# schematic.net
KiCad netlist of a schematic drawn in Altium Designer
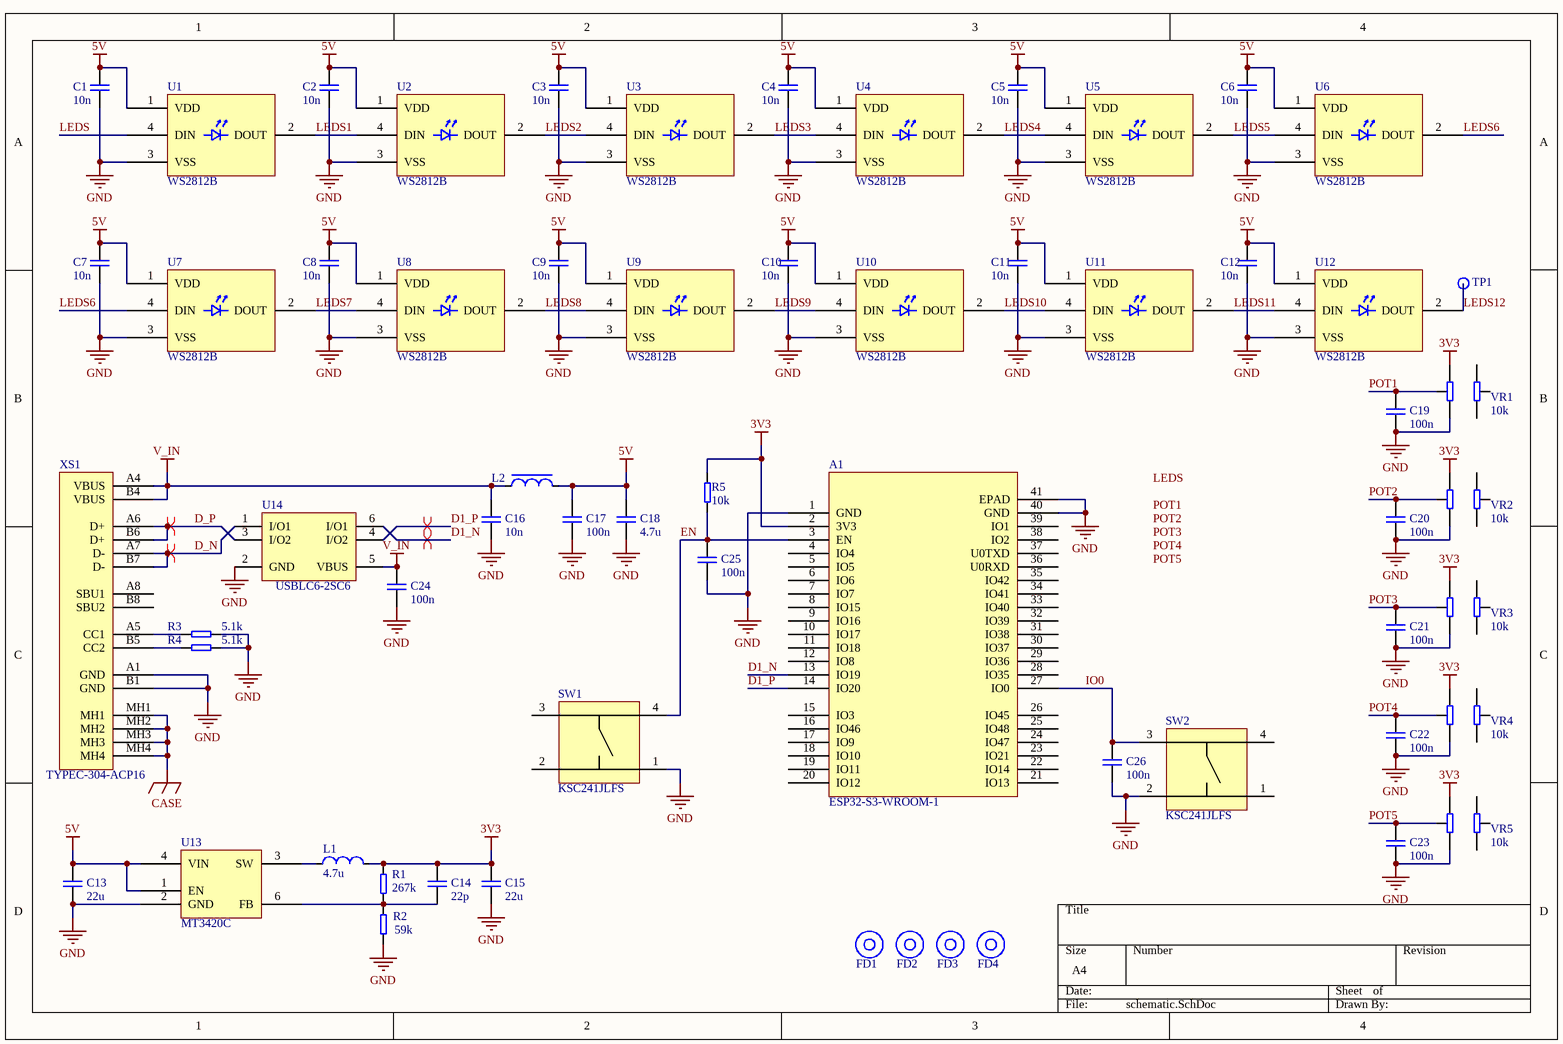
[diagram p0: schematic.SchDoc]

(export (version "E")
  (design (tool "Eeschema 10.0.6"))
  (components
    (comp (ref "A1")
      (value "ESP32-S3-WROOM-1")
      (footprint "ESP32-S3-WROOM-1")
      (description "2.4 GHz Wi-Fi (802.11 b/g/n) and Bluetooth® 5 (LE) module")
      (fields (field (name "MANUFACTURER") "espressif"))
      (libsource (lib "1") (part "ESP32-S3-WROOM-1"))
    )
    (comp (ref "C1")
      (value "10n")
      (footprint "C0805")
      (description "CAPACITOR")
      (libsource (lib "1") (part "Cap"))
    )
    (comp (ref "C2")
      (value "10n")
      (footprint "C0805")
      (description "CAPACITOR")
      (libsource (lib "1") (part "Cap"))
    )
    (comp (ref "C3")
      (value "10n")
      (footprint "C0805")
      (description "CAPACITOR")
      (libsource (lib "1") (part "Cap"))
    )
    (comp (ref "C4")
      (value "10n")
      (footprint "C0805")
      (description "CAPACITOR")
      (libsource (lib "1") (part "Cap"))
    )
    (comp (ref "C5")
      (value "10n")
      (footprint "C0805")
      (description "CAPACITOR")
      (libsource (lib "1") (part "Cap"))
    )
    (comp (ref "C6")
      (value "10n")
      (footprint "C0805")
      (description "CAPACITOR")
      (libsource (lib "1") (part "Cap"))
    )
    (comp (ref "C7")
      (value "10n")
      (footprint "C0805")
      (description "CAPACITOR")
      (libsource (lib "1") (part "Cap"))
    )
    (comp (ref "C8")
      (value "10n")
      (footprint "C0805")
      (description "CAPACITOR")
      (libsource (lib "1") (part "Cap"))
    )
    (comp (ref "C9")
      (value "10n")
      (footprint "C0805")
      (description "CAPACITOR")
      (libsource (lib "1") (part "Cap"))
    )
    (comp (ref "C10")
      (value "10n")
      (footprint "C0805")
      (description "CAPACITOR")
      (libsource (lib "1") (part "Cap"))
    )
    (comp (ref "C11")
      (value "10n")
      (footprint "C0805")
      (description "CAPACITOR")
      (libsource (lib "1") (part "Cap"))
    )
    (comp (ref "C12")
      (value "10n")
      (footprint "C0805")
      (description "CAPACITOR")
      (libsource (lib "1") (part "Cap"))
    )
    (comp (ref "C13")
      (value "22u")
      (footprint "C1210")
      (description "CAPACITOR")
      (libsource (lib "1") (part "Cap"))
    )
    (comp (ref "C14")
      (value "22p")
      (footprint "C0805")
      (description "CAPACITOR")
      (libsource (lib "1") (part "Cap"))
    )
    (comp (ref "C15")
      (value "22u")
      (footprint "C1210")
      (description "CAPACITOR")
      (libsource (lib "1") (part "Cap"))
    )
    (comp (ref "C16")
      (value "10n")
      (footprint "C0805")
      (description "CAPACITOR")
      (libsource (lib "1") (part "Cap"))
    )
    (comp (ref "C17")
      (value "100n")
      (footprint "C0805")
      (description "CAPACITOR")
      (libsource (lib "1") (part "Cap"))
    )
    (comp (ref "C18")
      (value "4.7u")
      (footprint "C0805")
      (description "CAPACITOR")
      (libsource (lib "1") (part "Cap"))
    )
    (comp (ref "C19")
      (value "100n")
      (footprint "C0805")
      (description "CAPACITOR")
      (libsource (lib "1") (part "Cap"))
    )
    (comp (ref "C20")
      (value "100n")
      (footprint "C0805")
      (description "CAPACITOR")
      (libsource (lib "1") (part "Cap"))
    )
    (comp (ref "C21")
      (value "100n")
      (footprint "C0805")
      (description "CAPACITOR")
      (libsource (lib "1") (part "Cap"))
    )
    (comp (ref "C22")
      (value "100n")
      (footprint "C0805")
      (description "CAPACITOR")
      (libsource (lib "1") (part "Cap"))
    )
    (comp (ref "C23")
      (value "100n")
      (footprint "C0805")
      (description "CAPACITOR")
      (libsource (lib "1") (part "Cap"))
    )
    (comp (ref "C24")
      (value "100n")
      (footprint "C0805")
      (description "CAPACITOR")
      (libsource (lib "1") (part "Cap"))
    )
    (comp (ref "C25")
      (value "100n")
      (footprint "C0805")
      (description "CAPACITOR")
      (libsource (lib "1") (part "Cap"))
    )
    (comp (ref "C26")
      (value "100n")
      (footprint "C0805")
      (description "CAPACITOR")
      (libsource (lib "1") (part "Cap"))
    )
    (comp (ref "FD1")
      (value "Fiducial")
      (footprint "Fiducial")
      (description "Fiducial marker")
      (libsource (lib "1") (part "Fiducial"))
    )
    (comp (ref "FD2")
      (value "Fiducial")
      (footprint "Fiducial")
      (description "Fiducial marker")
      (libsource (lib "1") (part "Fiducial"))
    )
    (comp (ref "FD3")
      (value "Fiducial")
      (footprint "Fiducial")
      (description "Fiducial marker")
      (libsource (lib "1") (part "Fiducial"))
    )
    (comp (ref "FD4")
      (value "Fiducial")
      (footprint "Fiducial")
      (description "Fiducial marker")
      (libsource (lib "1") (part "Fiducial"))
    )
    (comp (ref "L1")
      (value "4.7u")
      (footprint "ASPI-0630LR-4R7")
      (description "INDUCTOR")
      (libsource (lib "1") (part "Ind"))
    )
    (comp (ref "L2")
      (value "~")
      (footprint "C0805")
      (description "Ferrite Bead")
      (libsource (lib "1") (part "Ind"))
    )
    (comp (ref "R1")
      (value "267k")
      (footprint "R0805")
      (description "RESISTOR")
      (libsource (lib "1") (part "Res"))
    )
    (comp (ref "R2")
      (value "59k")
      (footprint "R0805")
      (description "RESISTOR")
      (libsource (lib "1") (part "Res"))
    )
    (comp (ref "R3")
      (value "5.1k")
      (footprint "R0805")
      (description "RESISTOR")
      (libsource (lib "1") (part "Res"))
    )
    (comp (ref "R4")
      (value "5.1k")
      (footprint "R0805")
      (description "RESISTOR")
      (libsource (lib "1") (part "Res"))
    )
    (comp (ref "R5")
      (value "10k")
      (footprint "R0805")
      (description "RESISTOR")
      (libsource (lib "1") (part "Res"))
    )
    (comp (ref "SW1")
      (value "KSC241JLFS")
      (footprint "KSC241JLFS")
      (description "SWITCH TACTILE SPST-NO 50mA @ 32VDC")
      (fields (field (name "MANUFACTURER") "C&K"))
      (libsource (lib "1") (part "KSC241JLFS"))
    )
    (comp (ref "SW2")
      (value "KSC241JLFS")
      (footprint "KSC241JLFS")
      (description "SWITCH TACTILE SPST-NO 50mA @ 32VDC")
      (fields (field (name "MANUFACTURER") "C&K"))
      (libsource (lib "1") (part "KSC241JLFS"))
    )
    (comp (ref "TP1")
      (value "Test Point")
      (footprint "Test-Point")
      (description "Test point")
      (libsource (lib "1") (part "Test Point"))
    )
    (comp (ref "U1")
      (value "WS2812B")
      (footprint "WS2812B")
      (description "LED RGB 800kHZ")
      (fields (field (name "MANUFACTURER") "Worldsemi"))
      (libsource (lib "1") (part "WS2812B"))
    )
    (comp (ref "U2")
      (value "WS2812B")
      (footprint "WS2812B")
      (description "LED RGB 800kHZ")
      (fields (field (name "MANUFACTURER") "Worldsemi"))
      (libsource (lib "1") (part "WS2812B"))
    )
    (comp (ref "U3")
      (value "WS2812B")
      (footprint "WS2812B")
      (description "LED RGB 800kHZ")
      (fields (field (name "MANUFACTURER") "Worldsemi"))
      (libsource (lib "1") (part "WS2812B"))
    )
    (comp (ref "U4")
      (value "WS2812B")
      (footprint "WS2812B")
      (description "LED RGB 800kHZ")
      (fields (field (name "MANUFACTURER") "Worldsemi"))
      (libsource (lib "1") (part "WS2812B"))
    )
    (comp (ref "U5")
      (value "WS2812B")
      (footprint "WS2812B")
      (description "LED RGB 800kHZ")
      (fields (field (name "MANUFACTURER") "Worldsemi"))
      (libsource (lib "1") (part "WS2812B"))
    )
    (comp (ref "U6")
      (value "WS2812B")
      (footprint "WS2812B")
      (description "LED RGB 800kHZ")
      (fields (field (name "MANUFACTURER") "Worldsemi"))
      (libsource (lib "1") (part "WS2812B"))
    )
    (comp (ref "U7")
      (value "WS2812B")
      (footprint "WS2812B")
      (description "LED RGB 800kHZ")
      (fields (field (name "MANUFACTURER") "Worldsemi"))
      (libsource (lib "1") (part "WS2812B"))
    )
    (comp (ref "U8")
      (value "WS2812B")
      (footprint "WS2812B")
      (description "LED RGB 800kHZ")
      (fields (field (name "MANUFACTURER") "Worldsemi"))
      (libsource (lib "1") (part "WS2812B"))
    )
    (comp (ref "U9")
      (value "WS2812B")
      (footprint "WS2812B")
      (description "LED RGB 800kHZ")
      (fields (field (name "MANUFACTURER") "Worldsemi"))
      (libsource (lib "1") (part "WS2812B"))
    )
    (comp (ref "U10")
      (value "WS2812B")
      (footprint "WS2812B")
      (description "LED RGB 800kHZ")
      (fields (field (name "MANUFACTURER") "Worldsemi"))
      (libsource (lib "1") (part "WS2812B"))
    )
    (comp (ref "U11")
      (value "WS2812B")
      (footprint "WS2812B")
      (description "LED RGB 800kHZ")
      (fields (field (name "MANUFACTURER") "Worldsemi"))
      (libsource (lib "1") (part "WS2812B"))
    )
    (comp (ref "U12")
      (value "WS2812B")
      (footprint "WS2812B")
      (description "LED RGB 800kHZ")
      (fields (field (name "MANUFACTURER") "Worldsemi"))
      (libsource (lib "1") (part "WS2812B"))
    )
    (comp (ref "U13")
      (value "MT3420C")
      (footprint "SOT23-6-MT3420C")
      (description "2A 2.3-6V Input 1.5MHz Synchronous Step-Down Converter")
      (fields (field (name "MANUFACTURER") "Aerosemi"))
      (libsource (lib "1") (part "MT3420C"))
    )
    (comp (ref "U14")
      (value "USBLC6-2SC6")
      (footprint "SOT23-6L-USBLC6-2SC6")
      (description "TVS DIODE 5.25V 17V SOT23-6")
      (fields (field (name "MANUFACTURER") "STMicroelectronics"))
      (libsource (lib "1") (part "USBLC6-2SC6"))
    )
    (comp (ref "VR1") (value "10k") (footprint "SC6080GH") (libsource (lib "1") (part "SC6080GH")))
    (comp (ref "VR2") (value "10k") (footprint "SC6080GH") (libsource (lib "1") (part "SC6080GH")))
    (comp (ref "VR3") (value "10k") (footprint "SC6080GH") (libsource (lib "1") (part "SC6080GH")))
    (comp (ref "VR4") (value "10k") (footprint "SC6080GH") (libsource (lib "1") (part "SC6080GH")))
    (comp (ref "VR5") (value "10k") (footprint "SC6080GH") (libsource (lib "1") (part "SC6080GH")))
    (comp (ref "XS1")
      (value "TYPEC-304-ACP16")
      (footprint "XUNPU_TYPEC-304-ACP16")
      (description "USB Type-C Compatible 16-position Right Angle Receptacle")
      (fields (field (name "MANUFACTURER") "XUNPU"))
      (libsource (lib "1") (part "TYPEC-304-ACP16"))
    )
  )
  (nets
    (net (code "1") (name "/D1_N") (class "Default")
      (node (ref "A1") (pin "13") (pinfunction "IO19_13") (pintype "passive"))
      (node (ref "U14") (pin "6") (pinfunction "I/O1_6") (pintype "passive"))
    )
    (net (code "2") (name "/D1_P") (class "Default")
      (node (ref "A1") (pin "14") (pinfunction "IO20_14") (pintype "passive"))
      (node (ref "U14") (pin "4") (pinfunction "I/O2_4") (pintype "passive"))
    )
    (net (code "3") (name "/D_N") (class "Default")
      (node (ref "U14") (pin "1") (pinfunction "I/O1_1") (pintype "passive"))
      (node (ref "XS1") (pin "A7") (pinfunction "D-_A7") (pintype "passive"))
      (node (ref "XS1") (pin "B7") (pinfunction "D-_B7") (pintype "passive"))
    )
    (net (code "4") (name "/D_P") (class "Default")
      (node (ref "U14") (pin "3") (pinfunction "I/O2_3") (pintype "passive"))
      (node (ref "XS1") (pin "A6") (pinfunction "D+_A6") (pintype "passive"))
      (node (ref "XS1") (pin "B6") (pinfunction "D+_B6") (pintype "passive"))
    )
    (net (code "5") (name "/EN") (class "Default")
      (node (ref "A1") (pin "3") (pinfunction "EN_3") (pintype "passive"))
      (node (ref "C25") (pin "2") (pinfunction "2_2") (pintype "passive"))
      (node (ref "R5") (pin "2") (pinfunction "2_2") (pintype "passive"))
      (node (ref "SW1") (pin "4") (pinfunction "4_4") (pintype "passive"))
    )
    (net (code "6") (name "/IO0") (class "Default")
      (node (ref "A1") (pin "27") (pinfunction "IO0_27") (pintype "passive"))
      (node (ref "C26") (pin "2") (pinfunction "2_2") (pintype "passive"))
      (node (ref "SW2") (pin "3") (pinfunction "3_3") (pintype "passive"))
    )
    (net (code "7") (name "/LEDS") (class "Default")
      (node (ref "U1") (pin "4") (pinfunction "DIN_4") (pintype "passive"))
    )
    (net (code "8") (name "/LEDS1") (class "Default")
      (node (ref "U1") (pin "2") (pinfunction "DOUT_2") (pintype "passive"))
      (node (ref "U2") (pin "4") (pinfunction "DIN_4") (pintype "passive"))
    )
    (net (code "9") (name "/LEDS2") (class "Default")
      (node (ref "U2") (pin "2") (pinfunction "DOUT_2") (pintype "passive"))
      (node (ref "U3") (pin "4") (pinfunction "DIN_4") (pintype "passive"))
    )
    (net (code "10") (name "/LEDS3") (class "Default")
      (node (ref "U3") (pin "2") (pinfunction "DOUT_2") (pintype "passive"))
      (node (ref "U4") (pin "4") (pinfunction "DIN_4") (pintype "passive"))
    )
    (net (code "11") (name "/LEDS4") (class "Default")
      (node (ref "U4") (pin "2") (pinfunction "DOUT_2") (pintype "passive"))
      (node (ref "U5") (pin "4") (pinfunction "DIN_4") (pintype "passive"))
    )
    (net (code "12") (name "/LEDS5") (class "Default")
      (node (ref "U5") (pin "2") (pinfunction "DOUT_2") (pintype "passive"))
      (node (ref "U6") (pin "4") (pinfunction "DIN_4") (pintype "passive"))
    )
    (net (code "13") (name "/LEDS6") (class "Default")
      (node (ref "U6") (pin "2") (pinfunction "DOUT_2") (pintype "passive"))
      (node (ref "U7") (pin "4") (pinfunction "DIN_4") (pintype "passive"))
    )
    (net (code "14") (name "/LEDS7") (class "Default")
      (node (ref "U7") (pin "2") (pinfunction "DOUT_2") (pintype "passive"))
      (node (ref "U8") (pin "4") (pinfunction "DIN_4") (pintype "passive"))
    )
    (net (code "15") (name "/LEDS8") (class "Default")
      (node (ref "U8") (pin "2") (pinfunction "DOUT_2") (pintype "passive"))
      (node (ref "U9") (pin "4") (pinfunction "DIN_4") (pintype "passive"))
    )
    (net (code "16") (name "/LEDS9") (class "Default")
      (node (ref "U10") (pin "4") (pinfunction "DIN_4") (pintype "passive"))
      (node (ref "U9") (pin "2") (pinfunction "DOUT_2") (pintype "passive"))
    )
    (net (code "17") (name "/LEDS10") (class "Default")
      (node (ref "U10") (pin "2") (pinfunction "DOUT_2") (pintype "passive"))
      (node (ref "U11") (pin "4") (pinfunction "DIN_4") (pintype "passive"))
    )
    (net (code "18") (name "/LEDS11") (class "Default")
      (node (ref "U11") (pin "2") (pinfunction "DOUT_2") (pintype "passive"))
      (node (ref "U12") (pin "4") (pinfunction "DIN_4") (pintype "passive"))
    )
    (net (code "19") (name "/LEDS12") (class "Default")
      (node (ref "TP1") (pin "0") (pinfunction "0_0") (pintype "passive"))
      (node (ref "U12") (pin "2") (pinfunction "DOUT_2") (pintype "passive"))
    )
    (net (code "20") (name "/POT1") (class "Default")
      (node (ref "C19") (pin "1") (pinfunction "1_1") (pintype "passive"))
      (node (ref "VR1") (pin "2") (pinfunction "2_2") (pintype "passive"))
    )
    (net (code "21") (name "/POT2") (class "Default")
      (node (ref "C20") (pin "1") (pinfunction "1_1") (pintype "passive"))
      (node (ref "VR2") (pin "2") (pinfunction "2_2") (pintype "passive"))
    )
    (net (code "22") (name "/POT3") (class "Default")
      (node (ref "C21") (pin "1") (pinfunction "1_1") (pintype "passive"))
      (node (ref "VR3") (pin "2") (pinfunction "2_2") (pintype "passive"))
    )
    (net (code "23") (name "/POT4") (class "Default")
      (node (ref "C22") (pin "1") (pinfunction "1_1") (pintype "passive"))
      (node (ref "VR4") (pin "2") (pinfunction "2_2") (pintype "passive"))
    )
    (net (code "24") (name "/POT5") (class "Default")
      (node (ref "C23") (pin "1") (pinfunction "1_1") (pintype "passive"))
      (node (ref "VR5") (pin "2") (pinfunction "2_2") (pintype "passive"))
    )
    (net (code "25") (name "3V3") (class "Default")
      (node (ref "A1") (pin "2") (pinfunction "3V3_2") (pintype "passive"))
      (node (ref "C14") (pin "2") (pinfunction "2_2") (pintype "passive"))
      (node (ref "C15") (pin "2") (pinfunction "2_2") (pintype "passive"))
      (node (ref "L1") (pin "2") (pinfunction "2_2") (pintype "passive"))
      (node (ref "R1") (pin "2") (pinfunction "2_2") (pintype "passive"))
      (node (ref "R5") (pin "1") (pinfunction "1_1") (pintype "passive"))
      (node (ref "VR1") (pin "1") (pinfunction "1_1") (pintype "passive"))
      (node (ref "VR2") (pin "1") (pinfunction "1_1") (pintype "passive"))
      (node (ref "VR3") (pin "1") (pinfunction "1_1") (pintype "passive"))
      (node (ref "VR4") (pin "1") (pinfunction "1_1") (pintype "passive"))
      (node (ref "VR5") (pin "1") (pinfunction "1_1") (pintype "passive"))
    )
    (net (code "26") (name "5V") (class "Default")
      (node (ref "C1") (pin "2") (pinfunction "2_2") (pintype "passive"))
      (node (ref "C10") (pin "2") (pinfunction "2_2") (pintype "passive"))
      (node (ref "C11") (pin "2") (pinfunction "2_2") (pintype "passive"))
      (node (ref "C12") (pin "2") (pinfunction "2_2") (pintype "passive"))
      (node (ref "C13") (pin "2") (pinfunction "2_2") (pintype "passive"))
      (node (ref "C17") (pin "2") (pinfunction "2_2") (pintype "passive"))
      (node (ref "C18") (pin "2") (pinfunction "2_2") (pintype "passive"))
      (node (ref "C2") (pin "2") (pinfunction "2_2") (pintype "passive"))
      (node (ref "C3") (pin "2") (pinfunction "2_2") (pintype "passive"))
      (node (ref "C4") (pin "2") (pinfunction "2_2") (pintype "passive"))
      (node (ref "C5") (pin "2") (pinfunction "2_2") (pintype "passive"))
      (node (ref "C6") (pin "2") (pinfunction "2_2") (pintype "passive"))
      (node (ref "C7") (pin "2") (pinfunction "2_2") (pintype "passive"))
      (node (ref "C8") (pin "2") (pinfunction "2_2") (pintype "passive"))
      (node (ref "C9") (pin "2") (pinfunction "2_2") (pintype "passive"))
      (node (ref "L2") (pin "2") (pinfunction "2_2") (pintype "passive"))
      (node (ref "U1") (pin "1") (pinfunction "VDD_1") (pintype "passive"))
      (node (ref "U10") (pin "1") (pinfunction "VDD_1") (pintype "passive"))
      (node (ref "U11") (pin "1") (pinfunction "VDD_1") (pintype "passive"))
      (node (ref "U12") (pin "1") (pinfunction "VDD_1") (pintype "passive"))
      (node (ref "U13") (pin "1") (pinfunction "EN_1") (pintype "passive"))
      (node (ref "U13") (pin "4") (pinfunction "VIN_4") (pintype "passive"))
      (node (ref "U2") (pin "1") (pinfunction "VDD_1") (pintype "passive"))
      (node (ref "U3") (pin "1") (pinfunction "VDD_1") (pintype "passive"))
      (node (ref "U4") (pin "1") (pinfunction "VDD_1") (pintype "passive"))
      (node (ref "U5") (pin "1") (pinfunction "VDD_1") (pintype "passive"))
      (node (ref "U6") (pin "1") (pinfunction "VDD_1") (pintype "passive"))
      (node (ref "U7") (pin "1") (pinfunction "VDD_1") (pintype "passive"))
      (node (ref "U8") (pin "1") (pinfunction "VDD_1") (pintype "passive"))
      (node (ref "U9") (pin "1") (pinfunction "VDD_1") (pintype "passive"))
    )
    (net (code "27") (name "CASE") (class "Default")
      (node (ref "XS1") (pin "MH1") (pinfunction "MH1_MH1") (pintype "passive"))
      (node (ref "XS1") (pin "MH2") (pinfunction "MH2_MH2") (pintype "passive"))
      (node (ref "XS1") (pin "MH3") (pinfunction "MH3_MH3") (pintype "passive"))
      (node (ref "XS1") (pin "MH4") (pinfunction "MH4_MH4") (pintype "passive"))
    )
    (net (code "28") (name "GND") (class "Default")
      (node (ref "A1") (pin "1") (pinfunction "GND_1") (pintype "passive"))
      (node (ref "A1") (pin "40") (pinfunction "GND_40") (pintype "passive"))
      (node (ref "A1") (pin "41") (pinfunction "EPAD_41") (pintype "passive"))
      (node (ref "C1") (pin "1") (pinfunction "1_1") (pintype "passive"))
      (node (ref "C10") (pin "1") (pinfunction "1_1") (pintype "passive"))
      (node (ref "C11") (pin "1") (pinfunction "1_1") (pintype "passive"))
      (node (ref "C12") (pin "1") (pinfunction "1_1") (pintype "passive"))
      (node (ref "C13") (pin "1") (pinfunction "1_1") (pintype "passive"))
      (node (ref "C15") (pin "1") (pinfunction "1_1") (pintype "passive"))
      (node (ref "C16") (pin "1") (pinfunction "1_1") (pintype "passive"))
      (node (ref "C17") (pin "1") (pinfunction "1_1") (pintype "passive"))
      (node (ref "C18") (pin "1") (pinfunction "1_1") (pintype "passive"))
      (node (ref "C19") (pin "2") (pinfunction "2_2") (pintype "passive"))
      (node (ref "C2") (pin "1") (pinfunction "1_1") (pintype "passive"))
      (node (ref "C20") (pin "2") (pinfunction "2_2") (pintype "passive"))
      (node (ref "C21") (pin "2") (pinfunction "2_2") (pintype "passive"))
      (node (ref "C22") (pin "2") (pinfunction "2_2") (pintype "passive"))
      (node (ref "C23") (pin "2") (pinfunction "2_2") (pintype "passive"))
      (node (ref "C24") (pin "1") (pinfunction "1_1") (pintype "passive"))
      (node (ref "C25") (pin "1") (pinfunction "1_1") (pintype "passive"))
      (node (ref "C26") (pin "1") (pinfunction "1_1") (pintype "passive"))
      (node (ref "C3") (pin "1") (pinfunction "1_1") (pintype "passive"))
      (node (ref "C4") (pin "1") (pinfunction "1_1") (pintype "passive"))
      (node (ref "C5") (pin "1") (pinfunction "1_1") (pintype "passive"))
      (node (ref "C6") (pin "1") (pinfunction "1_1") (pintype "passive"))
      (node (ref "C7") (pin "1") (pinfunction "1_1") (pintype "passive"))
      (node (ref "C8") (pin "1") (pinfunction "1_1") (pintype "passive"))
      (node (ref "C9") (pin "1") (pinfunction "1_1") (pintype "passive"))
      (node (ref "R2") (pin "1") (pinfunction "1_1") (pintype "passive"))
      (node (ref "R3") (pin "1") (pinfunction "1_1") (pintype "passive"))
      (node (ref "R4") (pin "1") (pinfunction "1_1") (pintype "passive"))
      (node (ref "SW1") (pin "1") (pinfunction "1_1") (pintype "passive"))
      (node (ref "SW2") (pin "2") (pinfunction "2_2") (pintype "passive"))
      (node (ref "U1") (pin "3") (pinfunction "VSS_3") (pintype "passive"))
      (node (ref "U10") (pin "3") (pinfunction "VSS_3") (pintype "passive"))
      (node (ref "U11") (pin "3") (pinfunction "VSS_3") (pintype "passive"))
      (node (ref "U12") (pin "3") (pinfunction "VSS_3") (pintype "passive"))
      (node (ref "U13") (pin "2") (pinfunction "GND_2") (pintype "passive"))
      (node (ref "U14") (pin "2") (pinfunction "GND_2") (pintype "passive"))
      (node (ref "U2") (pin "3") (pinfunction "VSS_3") (pintype "passive"))
      (node (ref "U3") (pin "3") (pinfunction "VSS_3") (pintype "passive"))
      (node (ref "U4") (pin "3") (pinfunction "VSS_3") (pintype "passive"))
      (node (ref "U5") (pin "3") (pinfunction "VSS_3") (pintype "passive"))
      (node (ref "U6") (pin "3") (pinfunction "VSS_3") (pintype "passive"))
      (node (ref "U7") (pin "3") (pinfunction "VSS_3") (pintype "passive"))
      (node (ref "U8") (pin "3") (pinfunction "VSS_3") (pintype "passive"))
      (node (ref "U9") (pin "3") (pinfunction "VSS_3") (pintype "passive"))
      (node (ref "VR1") (pin "3") (pinfunction "3_3") (pintype "passive"))
      (node (ref "VR2") (pin "3") (pinfunction "3_3") (pintype "passive"))
      (node (ref "VR3") (pin "3") (pinfunction "3_3") (pintype "passive"))
      (node (ref "VR4") (pin "3") (pinfunction "3_3") (pintype "passive"))
      (node (ref "VR5") (pin "3") (pinfunction "3_3") (pintype "passive"))
      (node (ref "XS1") (pin "A1") (pinfunction "GND_A1") (pintype "passive"))
      (node (ref "XS1") (pin "B1") (pinfunction "GND_B1") (pintype "passive"))
    )
    (net (code "29") (name "Net-(U13-FB)") (class "Default")
      (node (ref "C14") (pin "1") (pinfunction "1_1") (pintype "passive"))
      (node (ref "R1") (pin "1") (pinfunction "1_1") (pintype "passive"))
      (node (ref "R2") (pin "2") (pinfunction "2_2") (pintype "passive"))
      (node (ref "U13") (pin "6") (pinfunction "FB_6") (pintype "passive"))
    )
    (net (code "30") (name "Net-(U13-SW)") (class "Default")
      (node (ref "L1") (pin "1") (pinfunction "1_1") (pintype "passive"))
      (node (ref "U13") (pin "3") (pinfunction "SW_3") (pintype "passive"))
    )
    (net (code "31") (name "Net-(XS1-CC1)") (class "Default")
      (node (ref "R3") (pin "2") (pinfunction "2_2") (pintype "passive"))
      (node (ref "XS1") (pin "A5") (pinfunction "CC1_A5") (pintype "passive"))
    )
    (net (code "32") (name "Net-(XS1-CC2)") (class "Default")
      (node (ref "R4") (pin "2") (pinfunction "2_2") (pintype "passive"))
      (node (ref "XS1") (pin "B5") (pinfunction "CC2_B5") (pintype "passive"))
    )
    (net (code "33") (name "V_IN") (class "Default")
      (node (ref "C16") (pin "2") (pinfunction "2_2") (pintype "passive"))
      (node (ref "C24") (pin "2") (pinfunction "2_2") (pintype "passive"))
      (node (ref "L2") (pin "1") (pinfunction "1_1") (pintype "passive"))
      (node (ref "U14") (pin "5") (pinfunction "VBUS_5") (pintype "passive"))
      (node (ref "XS1") (pin "A4") (pinfunction "VBUS_A4") (pintype "passive"))
      (node (ref "XS1") (pin "B4") (pinfunction "VBUS_B4") (pintype "passive"))
    )
    (net (code "34") (name "unconnected-(A1-IO1-Pad39)") (class "Default")
      (node (ref "A1") (pin "39") (pinfunction "IO1_39") (pintype "passive"))
    )
    (net (code "35") (name "unconnected-(A1-IO2-Pad38)") (class "Default")
      (node (ref "A1") (pin "38") (pinfunction "IO2_38") (pintype "passive"))
    )
    (net (code "36") (name "unconnected-(A1-IO3-Pad15)") (class "Default")
      (node (ref "A1") (pin "15") (pinfunction "IO3_15") (pintype "passive"))
    )
    (net (code "37") (name "unconnected-(A1-IO4-Pad4)") (class "Default")
      (node (ref "A1") (pin "4") (pinfunction "IO4_4") (pintype "passive"))
    )
    (net (code "38") (name "unconnected-(A1-IO5-Pad5)") (class "Default")
      (node (ref "A1") (pin "5") (pinfunction "IO5_5") (pintype "passive"))
    )
    (net (code "39") (name "unconnected-(A1-IO6-Pad6)") (class "Default")
      (node (ref "A1") (pin "6") (pinfunction "IO6_6") (pintype "passive"))
    )
    (net (code "40") (name "unconnected-(A1-IO7-Pad7)") (class "Default")
      (node (ref "A1") (pin "7") (pinfunction "IO7_7") (pintype "passive"))
    )
    (net (code "41") (name "unconnected-(A1-IO8-Pad12)") (class "Default")
      (node (ref "A1") (pin "12") (pinfunction "IO8_12") (pintype "passive"))
    )
    (net (code "42") (name "unconnected-(A1-IO9-Pad17)") (class "Default")
      (node (ref "A1") (pin "17") (pinfunction "IO9_17") (pintype "passive"))
    )
    (net (code "43") (name "unconnected-(A1-IO10-Pad18)") (class "Default")
      (node (ref "A1") (pin "18") (pinfunction "IO10_18") (pintype "passive"))
    )
    (net (code "44") (name "unconnected-(A1-IO11-Pad19)") (class "Default")
      (node (ref "A1") (pin "19") (pinfunction "IO11_19") (pintype "passive"))
    )
    (net (code "45") (name "unconnected-(A1-IO12-Pad20)") (class "Default")
      (node (ref "A1") (pin "20") (pinfunction "IO12_20") (pintype "passive"))
    )
    (net (code "46") (name "unconnected-(A1-IO13-Pad21)") (class "Default")
      (node (ref "A1") (pin "21") (pinfunction "IO13_21") (pintype "passive"))
    )
    (net (code "47") (name "unconnected-(A1-IO14-Pad22)") (class "Default")
      (node (ref "A1") (pin "22") (pinfunction "IO14_22") (pintype "passive"))
    )
    (net (code "48") (name "unconnected-(A1-IO15-Pad8)") (class "Default")
      (node (ref "A1") (pin "8") (pinfunction "IO15_8") (pintype "passive"))
    )
    (net (code "49") (name "unconnected-(A1-IO16-Pad9)") (class "Default")
      (node (ref "A1") (pin "9") (pinfunction "IO16_9") (pintype "passive"))
    )
    (net (code "50") (name "unconnected-(A1-IO17-Pad10)") (class "Default")
      (node (ref "A1") (pin "10") (pinfunction "IO17_10") (pintype "passive"))
    )
    (net (code "51") (name "unconnected-(A1-IO18-Pad11)") (class "Default")
      (node (ref "A1") (pin "11") (pinfunction "IO18_11") (pintype "passive"))
    )
    (net (code "52") (name "unconnected-(A1-IO21-Pad23)") (class "Default")
      (node (ref "A1") (pin "23") (pinfunction "IO21_23") (pintype "passive"))
    )
    (net (code "53") (name "unconnected-(A1-IO35-Pad28)") (class "Default")
      (node (ref "A1") (pin "28") (pinfunction "IO35_28") (pintype "passive"))
    )
    (net (code "54") (name "unconnected-(A1-IO36-Pad29)") (class "Default")
      (node (ref "A1") (pin "29") (pinfunction "IO36_29") (pintype "passive"))
    )
    (net (code "55") (name "unconnected-(A1-IO37-Pad30)") (class "Default")
      (node (ref "A1") (pin "30") (pinfunction "IO37_30") (pintype "passive"))
    )
    (net (code "56") (name "unconnected-(A1-IO38-Pad31)") (class "Default")
      (node (ref "A1") (pin "31") (pinfunction "IO38_31") (pintype "passive"))
    )
    (net (code "57") (name "unconnected-(A1-IO39-Pad32)") (class "Default")
      (node (ref "A1") (pin "32") (pinfunction "IO39_32") (pintype "passive"))
    )
    (net (code "58") (name "unconnected-(A1-IO40-Pad33)") (class "Default")
      (node (ref "A1") (pin "33") (pinfunction "IO40_33") (pintype "passive"))
    )
    (net (code "59") (name "unconnected-(A1-IO41-Pad34)") (class "Default")
      (node (ref "A1") (pin "34") (pinfunction "IO41_34") (pintype "passive"))
    )
    (net (code "60") (name "unconnected-(A1-IO42-Pad35)") (class "Default")
      (node (ref "A1") (pin "35") (pinfunction "IO42_35") (pintype "passive"))
    )
    (net (code "61") (name "unconnected-(A1-IO45-Pad26)") (class "Default")
      (node (ref "A1") (pin "26") (pinfunction "IO45_26") (pintype "passive"))
    )
    (net (code "62") (name "unconnected-(A1-IO46-Pad16)") (class "Default")
      (node (ref "A1") (pin "16") (pinfunction "IO46_16") (pintype "passive"))
    )
    (net (code "63") (name "unconnected-(A1-IO47-Pad24)") (class "Default")
      (node (ref "A1") (pin "24") (pinfunction "IO47_24") (pintype "passive"))
    )
    (net (code "64") (name "unconnected-(A1-IO48-Pad25)") (class "Default")
      (node (ref "A1") (pin "25") (pinfunction "IO48_25") (pintype "passive"))
    )
    (net (code "65") (name "unconnected-(A1-U0RXD-Pad36)") (class "Default")
      (node (ref "A1") (pin "36") (pinfunction "U0RXD_36") (pintype "passive"))
    )
    (net (code "66") (name "unconnected-(A1-U0TXD-Pad37)") (class "Default")
      (node (ref "A1") (pin "37") (pinfunction "U0TXD_37") (pintype "passive"))
    )
    (net (code "67") (name "unconnected-(FD1-Pad1)") (class "Default")
      (node (ref "FD1") (pin "1") (pinfunction "1_1") (pintype "passive"))
    )
    (net (code "68") (name "unconnected-(FD2-Pad1)") (class "Default")
      (node (ref "FD2") (pin "1") (pinfunction "1_1") (pintype "passive"))
    )
    (net (code "69") (name "unconnected-(FD3-Pad1)") (class "Default")
      (node (ref "FD3") (pin "1") (pinfunction "1_1") (pintype "passive"))
    )
    (net (code "70") (name "unconnected-(FD4-Pad1)") (class "Default")
      (node (ref "FD4") (pin "1") (pinfunction "1_1") (pintype "passive"))
    )
    (net (code "71") (name "unconnected-(SW1-Pad2)") (class "Default")
      (node (ref "SW1") (pin "2") (pinfunction "2_2") (pintype "passive"))
    )
    (net (code "72") (name "unconnected-(SW1-Pad3)") (class "Default")
      (node (ref "SW1") (pin "3") (pinfunction "3_3") (pintype "passive"))
    )
    (net (code "73") (name "unconnected-(SW2-Pad1)") (class "Default")
      (node (ref "SW2") (pin "1") (pinfunction "1_1") (pintype "passive"))
    )
    (net (code "74") (name "unconnected-(SW2-Pad4)") (class "Default")
      (node (ref "SW2") (pin "4") (pinfunction "4_4") (pintype "passive"))
    )
    (net (code "75") (name "unconnected-(VR1-Pad1')") (class "Default")
      (node (ref "VR1") (pin "1'") (pinfunction "1'_1'") (pintype "passive"))
    )
    (net (code "76") (name "unconnected-(VR1-Pad2')") (class "Default")
      (node (ref "VR1") (pin "2'") (pinfunction "2'_2'") (pintype "passive"))
    )
    (net (code "77") (name "unconnected-(VR1-Pad3')") (class "Default")
      (node (ref "VR1") (pin "3'") (pinfunction "3'_3'") (pintype "passive"))
    )
    (net (code "78") (name "unconnected-(VR2-Pad1')") (class "Default")
      (node (ref "VR2") (pin "1'") (pinfunction "1'_1'") (pintype "passive"))
    )
    (net (code "79") (name "unconnected-(VR2-Pad2')") (class "Default")
      (node (ref "VR2") (pin "2'") (pinfunction "2'_2'") (pintype "passive"))
    )
    (net (code "80") (name "unconnected-(VR2-Pad3')") (class "Default")
      (node (ref "VR2") (pin "3'") (pinfunction "3'_3'") (pintype "passive"))
    )
    (net (code "81") (name "unconnected-(VR3-Pad1')") (class "Default")
      (node (ref "VR3") (pin "1'") (pinfunction "1'_1'") (pintype "passive"))
    )
    (net (code "82") (name "unconnected-(VR3-Pad2')") (class "Default")
      (node (ref "VR3") (pin "2'") (pinfunction "2'_2'") (pintype "passive"))
    )
    (net (code "83") (name "unconnected-(VR3-Pad3')") (class "Default")
      (node (ref "VR3") (pin "3'") (pinfunction "3'_3'") (pintype "passive"))
    )
    (net (code "84") (name "unconnected-(VR4-Pad1')") (class "Default")
      (node (ref "VR4") (pin "1'") (pinfunction "1'_1'") (pintype "passive"))
    )
    (net (code "85") (name "unconnected-(VR4-Pad2')") (class "Default")
      (node (ref "VR4") (pin "2'") (pinfunction "2'_2'") (pintype "passive"))
    )
    (net (code "86") (name "unconnected-(VR4-Pad3')") (class "Default")
      (node (ref "VR4") (pin "3'") (pinfunction "3'_3'") (pintype "passive"))
    )
    (net (code "87") (name "unconnected-(VR5-Pad1')") (class "Default")
      (node (ref "VR5") (pin "1'") (pinfunction "1'_1'") (pintype "passive"))
    )
    (net (code "88") (name "unconnected-(VR5-Pad2')") (class "Default")
      (node (ref "VR5") (pin "2'") (pinfunction "2'_2'") (pintype "passive"))
    )
    (net (code "89") (name "unconnected-(VR5-Pad3')") (class "Default")
      (node (ref "VR5") (pin "3'") (pinfunction "3'_3'") (pintype "passive"))
    )
    (net (code "90") (name "unconnected-(XS1-SBU1-PadA8)") (class "Default")
      (node (ref "XS1") (pin "A8") (pinfunction "SBU1_A8") (pintype "passive"))
    )
    (net (code "91") (name "unconnected-(XS1-SBU2-PadB8)") (class "Default")
      (node (ref "XS1") (pin "B8") (pinfunction "SBU2_B8") (pintype "passive"))
    )
  )
)
